# switch_board.net
KiCad netlist of a schematic drawn in EAGLE
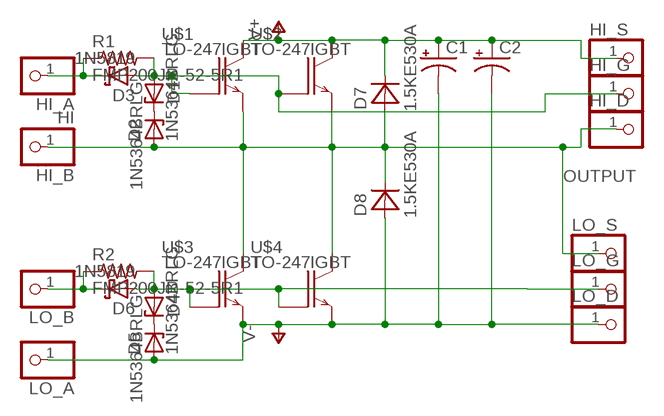
[diagram p0: schematic, sheet 1]

(export (version "E")
  (design (tool "Eeschema 10.0.6"))
  (components
    (comp (ref "C1")
      (value "CPOL-USTAP5-45")
      (footprint "eagle-import:TAP5-45")
      (libsource (lib "eagle-import") (part "CPOL-USTAP5-45"))
    )
    (comp (ref "C2")
      (value "CPOL-USTAP5-45")
      (footprint "eagle-import:TAP5-45")
      (libsource (lib "eagle-import") (part "CPOL-USTAP5-45"))
    )
    (comp (ref "D1")
      (value "1N5364BRLG")
      (footprint "eagle-import:DIOAD1576W109L863D349B")
      (libsource (lib "eagle-import") (part "1N5364BRLG"))
    )
    (comp (ref "D2")
      (value "1N5364BRLG")
      (footprint "eagle-import:DIOAD1576W109L863D349B")
      (libsource (lib "eagle-import") (part "1N5364BRLG"))
    )
    (comp (ref "D3")
      (value "1N5819")
      (footprint "eagle-import:DIOAD1138W86L470D235B")
      (libsource (lib "eagle-import") (part "1N5819"))
    )
    (comp (ref "D4")
      (value "1N5364BRLG")
      (footprint "eagle-import:DIOAD1576W109L863D349B")
      (libsource (lib "eagle-import") (part "1N5364BRLG"))
    )
    (comp (ref "D5")
      (value "1N5364BRLG")
      (footprint "eagle-import:DIOAD1576W109L863D349B")
      (libsource (lib "eagle-import") (part "1N5364BRLG"))
    )
    (comp (ref "D6")
      (value "1N5819")
      (footprint "eagle-import:DIOAD1138W86L470D235B")
      (libsource (lib "eagle-import") (part "1N5819"))
    )
    (comp (ref "D7")
      (value "1.5KE530A")
      (footprint "eagle-import:DIOAD1631W107L835D505B")
      (libsource (lib "eagle-import") (part "1.5KE530A"))
    )
    (comp (ref "D8")
      (value "1.5KE530A")
      (footprint "eagle-import:DIOAD1631W107L835D505B")
      (libsource (lib "eagle-import") (part "1.5KE530A"))
    )
    (comp (ref "HI_A")
      (value "PINHD-1X1")
      (footprint "eagle-import:1X01")
      (libsource (lib "eagle-import") (part "PINHD-1X1"))
    )
    (comp (ref "HI_B")
      (value "HI")
      (footprint "eagle-import:1X01")
      (libsource (lib "eagle-import") (part "PINHD-1X1"))
    )
    (comp (ref "HI_D")
      (value "PINHD-1X1")
      (footprint "eagle-import:1X01")
      (libsource (lib "eagle-import") (part "PINHD-1X1"))
    )
    (comp (ref "HI_G")
      (value "PINHD-1X1")
      (footprint "eagle-import:1X01")
      (libsource (lib "eagle-import") (part "PINHD-1X1"))
    )
    (comp (ref "HI_S")
      (value "PINHD-1X1")
      (footprint "eagle-import:1X01")
      (libsource (lib "eagle-import") (part "PINHD-1X1"))
    )
    (comp (ref "LO_A")
      (value "PINHD-1X1")
      (footprint "eagle-import:1X01")
      (libsource (lib "eagle-import") (part "PINHD-1X1"))
    )
    (comp (ref "LO_B")
      (value "PINHD-1X1")
      (footprint "eagle-import:1X01")
      (libsource (lib "eagle-import") (part "PINHD-1X1"))
    )
    (comp (ref "LO_D")
      (value "PINHD-1X1")
      (footprint "eagle-import:1X01")
      (libsource (lib "eagle-import") (part "PINHD-1X1"))
    )
    (comp (ref "LO_G")
      (value "PINHD-1X1")
      (footprint "eagle-import:1X01")
      (libsource (lib "eagle-import") (part "PINHD-1X1"))
    )
    (comp (ref "LO_S")
      (value "PINHD-1X1")
      (footprint "eagle-import:1X01")
      (libsource (lib "eagle-import") (part "PINHD-1X1"))
    )
    (comp (ref "R1")
      (value "FMP200JR-52-5R1")
      (footprint "eagle-import:RESAD1260W55L900D390B")
      (libsource (lib "eagle-import") (part "FMP200JR-52-5R1"))
    )
    (comp (ref "R2")
      (value "FMP200JR-52-5R1")
      (footprint "eagle-import:RESAD1260W55L900D390B")
      (libsource (lib "eagle-import") (part "FMP200JR-52-5R1"))
    )
    (comp (ref "U$1")
      (value "TO-247IGBT")
      (footprint "eagle-import:TO-247")
      (libsource (lib "eagle-import") (part "TO-247IGBT"))
    )
    (comp (ref "U$2")
      (value "TO-247IGBT")
      (footprint "eagle-import:TO-247")
      (libsource (lib "eagle-import") (part "TO-247IGBT"))
    )
    (comp (ref "U$3")
      (value "TO-247IGBT")
      (footprint "eagle-import:TO-247")
      (libsource (lib "eagle-import") (part "TO-247IGBT"))
    )
    (comp (ref "U$4")
      (value "TO-247IGBT")
      (footprint "eagle-import:TO-247")
      (libsource (lib "eagle-import") (part "TO-247IGBT"))
    )
  )
  (nets
    (net (code "1") (name "/OUTPUT") (class "Default")
      (node (ref "D2") (pin "2") (pinfunction "A_2") (pintype "passive"))
      (node (ref "D7") (pin "2") (pinfunction "A_2") (pintype "passive"))
      (node (ref "D8") (pin "1") (pinfunction "C_1") (pintype "passive"))
      (node (ref "HI_B") (pin "1") (pinfunction "1_1") (pintype "passive"))
      (node (ref "HI_D") (pin "1") (pinfunction "1_1") (pintype "passive"))
      (node (ref "LO_S") (pin "1") (pinfunction "1_1") (pintype "passive"))
      (node (ref "U$1") (pin "E") (pinfunction "E_E") (pintype "passive"))
      (node (ref "U$2") (pin "E") (pinfunction "E_E") (pintype "passive"))
      (node (ref "U$3") (pin "C") (pinfunction "C_C") (pintype "passive"))
      (node (ref "U$4") (pin "C") (pinfunction "C_C") (pintype "passive"))
    )
    (net (code "2") (name "Net-(D1-A)") (class "Default")
      (node (ref "D1") (pin "2") (pinfunction "A_2") (pintype "passive"))
      (node (ref "D3") (pin "2") (pinfunction "A_2") (pintype "passive"))
      (node (ref "HI_G") (pin "1") (pinfunction "1_1") (pintype "passive"))
      (node (ref "R1") (pin "2") (pinfunction "2_2") (pintype "passive"))
      (node (ref "U$1") (pin "G") (pinfunction "G_G") (pintype "passive"))
      (node (ref "U$2") (pin "G") (pinfunction "G_G") (pintype "passive"))
    )
    (net (code "3") (name "Net-(D1-C)") (class "Default")
      (node (ref "D1") (pin "1") (pinfunction "C_1") (pintype "passive"))
      (node (ref "D2") (pin "1") (pinfunction "C_1") (pintype "passive"))
    )
    (net (code "4") (name "Net-(D3-C)") (class "Default")
      (node (ref "D3") (pin "1") (pinfunction "C_1") (pintype "passive"))
      (node (ref "HI_A") (pin "1") (pinfunction "1_1") (pintype "passive"))
      (node (ref "R1") (pin "1") (pinfunction "1_1") (pintype "passive"))
    )
    (net (code "5") (name "Net-(D4-A)") (class "Default")
      (node (ref "D4") (pin "2") (pinfunction "A_2") (pintype "passive"))
      (node (ref "D6") (pin "2") (pinfunction "A_2") (pintype "passive"))
      (node (ref "LO_G") (pin "1") (pinfunction "1_1") (pintype "passive"))
      (node (ref "R2") (pin "2") (pinfunction "2_2") (pintype "passive"))
      (node (ref "U$3") (pin "G") (pinfunction "G_G") (pintype "passive"))
      (node (ref "U$4") (pin "G") (pinfunction "G_G") (pintype "passive"))
    )
    (net (code "6") (name "Net-(D4-C)") (class "Default")
      (node (ref "D4") (pin "1") (pinfunction "C_1") (pintype "passive"))
      (node (ref "D5") (pin "1") (pinfunction "C_1") (pintype "passive"))
    )
    (net (code "7") (name "Net-(D6-C)") (class "Default")
      (node (ref "D6") (pin "1") (pinfunction "C_1") (pintype "passive"))
      (node (ref "LO_B") (pin "1") (pinfunction "1_1") (pintype "passive"))
      (node (ref "R2") (pin "1") (pinfunction "1_1") (pintype "passive"))
    )
    (net (code "8") (name "V+") (class "Default")
      (node (ref "C1") (pin "+") (pinfunction "+_+") (pintype "passive"))
      (node (ref "C2") (pin "+") (pinfunction "+_+") (pintype "passive"))
      (node (ref "D7") (pin "1") (pinfunction "C_1") (pintype "passive"))
      (node (ref "HI_S") (pin "1") (pinfunction "1_1") (pintype "passive"))
      (node (ref "U$1") (pin "C") (pinfunction "C_C") (pintype "passive"))
      (node (ref "U$2") (pin "C") (pinfunction "C_C") (pintype "passive"))
    )
    (net (code "9") (name "V-") (class "Default")
      (node (ref "C1") (pin "-") (pinfunction "-_-") (pintype "passive"))
      (node (ref "C2") (pin "-") (pinfunction "-_-") (pintype "passive"))
      (node (ref "D5") (pin "2") (pinfunction "A_2") (pintype "passive"))
      (node (ref "D8") (pin "2") (pinfunction "A_2") (pintype "passive"))
      (node (ref "LO_A") (pin "1") (pinfunction "1_1") (pintype "passive"))
      (node (ref "LO_D") (pin "1") (pinfunction "1_1") (pintype "passive"))
      (node (ref "U$3") (pin "E") (pinfunction "E_E") (pintype "passive"))
      (node (ref "U$4") (pin "E") (pinfunction "E_E") (pintype "passive"))
    )
  )
)
